# design.net
KiCad netlist of a schematic drawn in Altium Designer
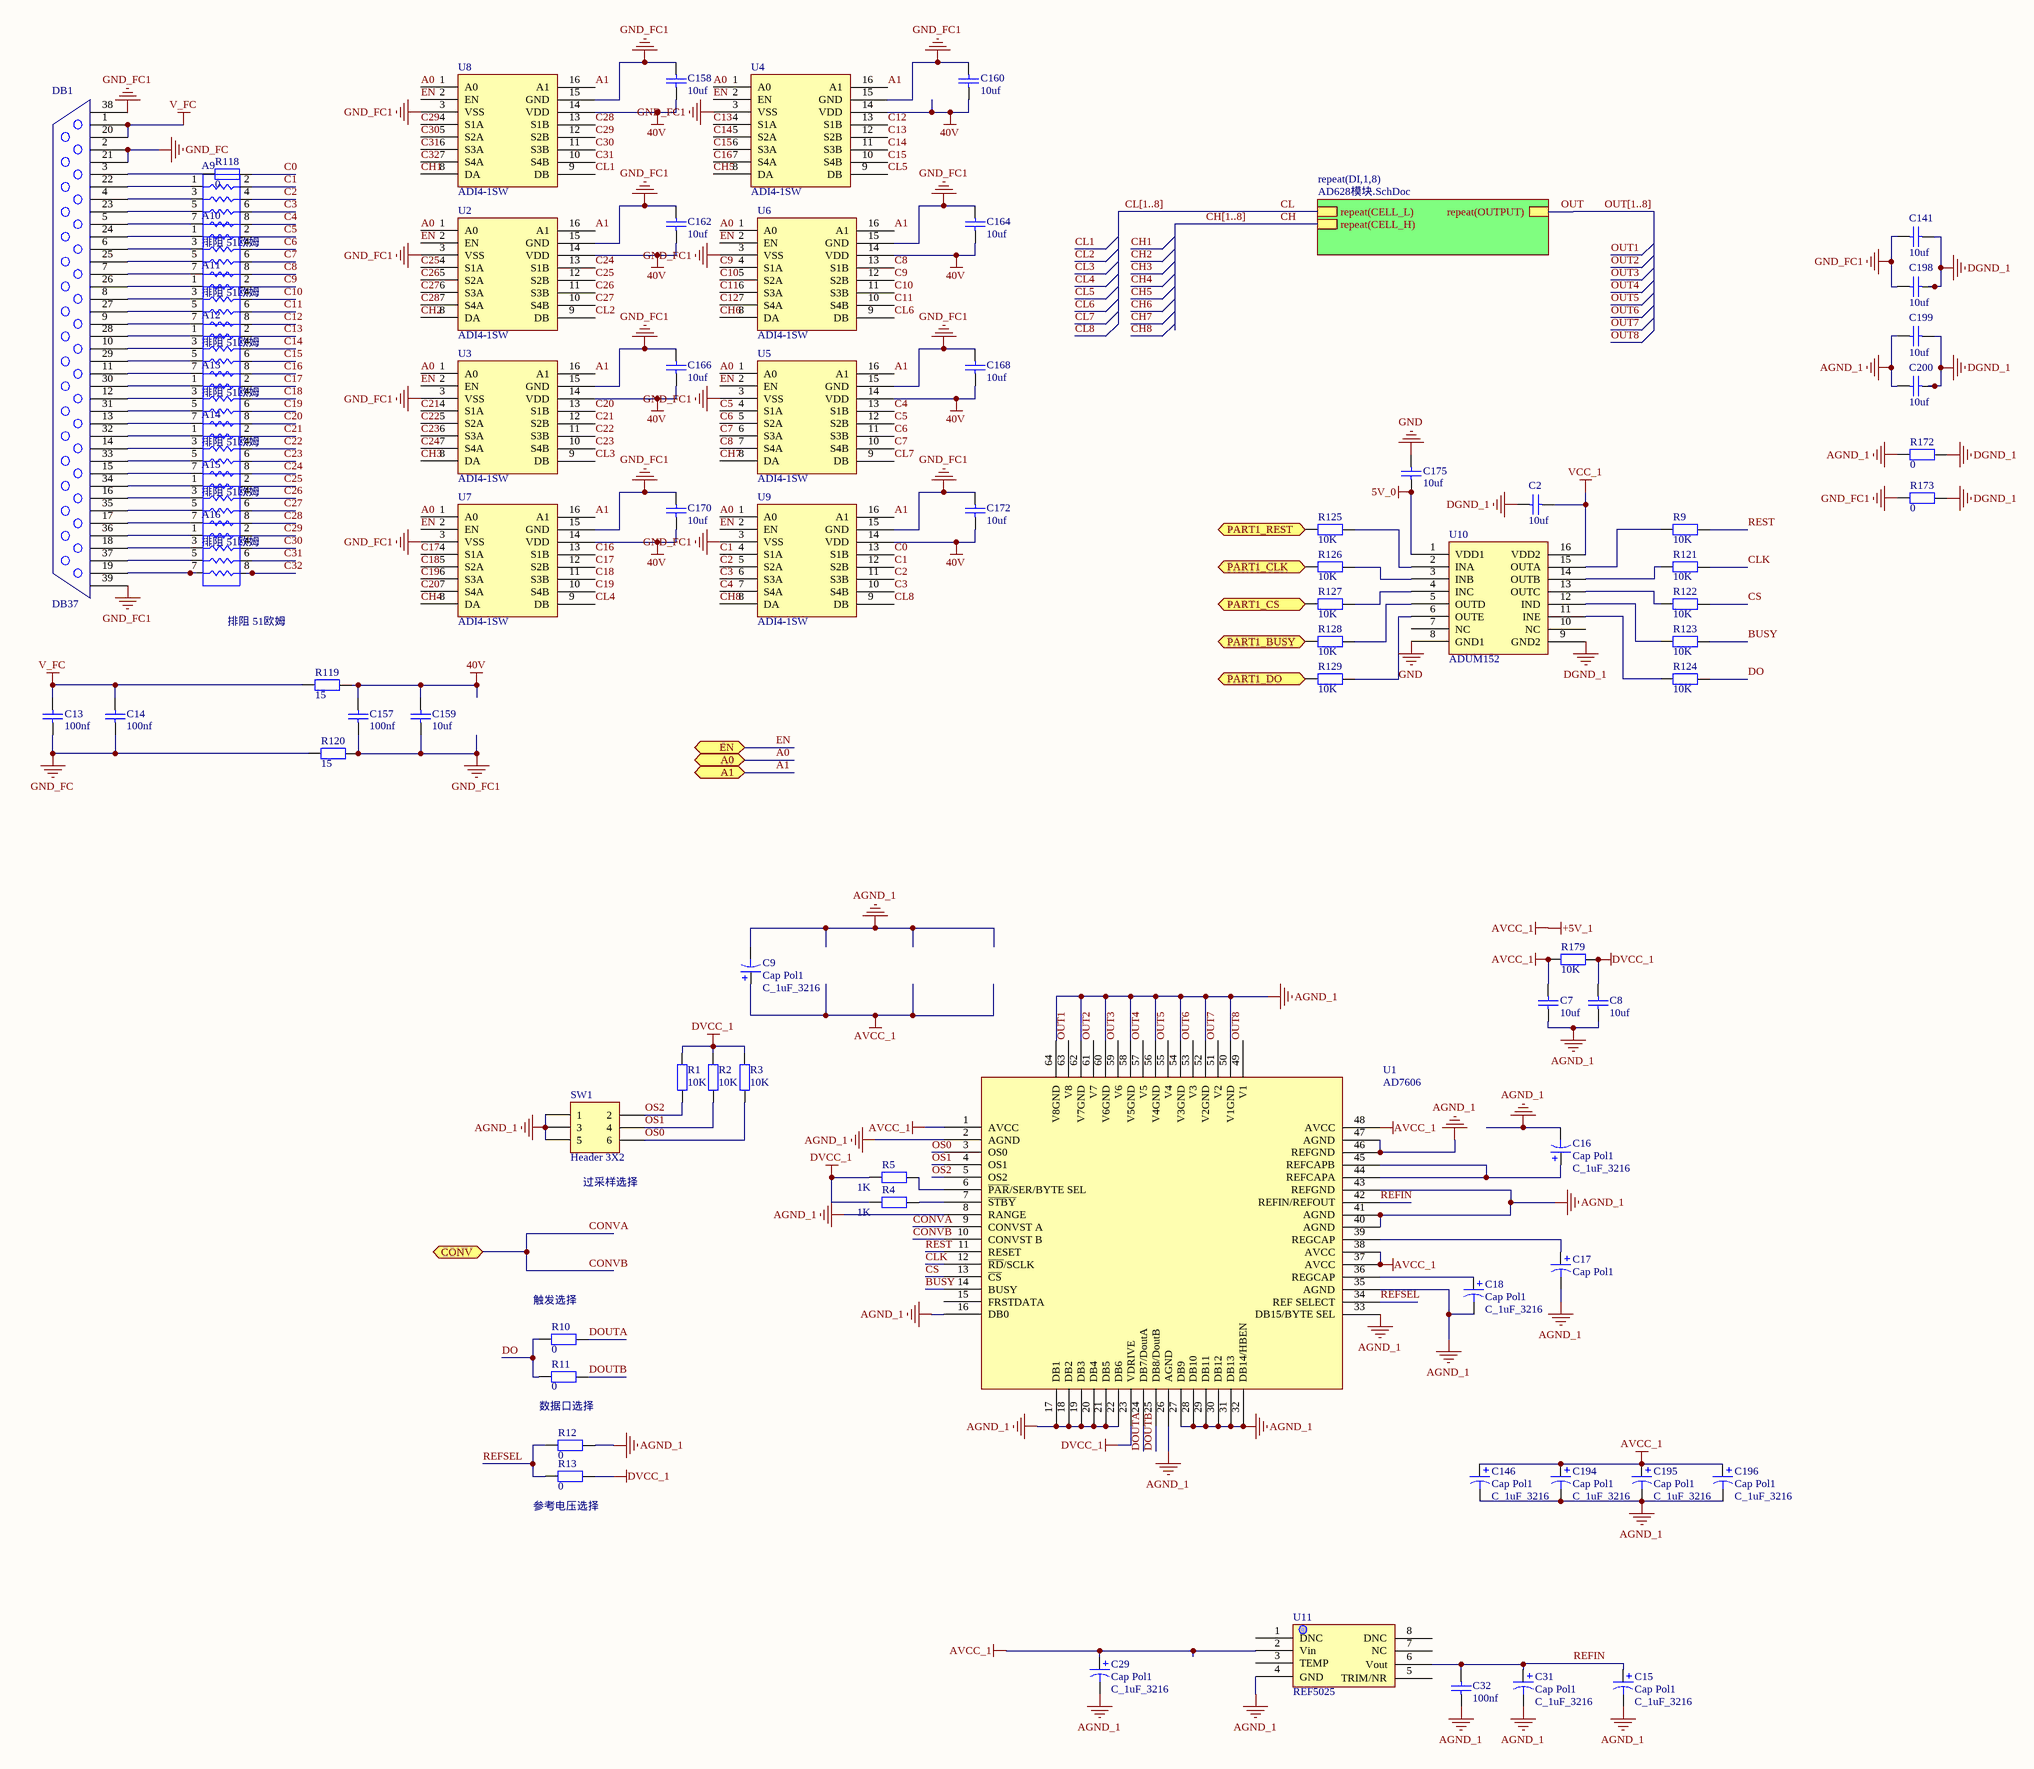
[diagram p0: 电池电压检测.SchDoc]

(export (version "E")
  (design (tool "Eeschema 10.0.6"))
  (components
    (comp (ref "A9")
      (value "排阻 51欧姆")
      (footprint "RCA03-4D")
      (libsource (lib "AD7606V23A") (part "RESPACK5"))
    )
    (comp (ref "A10")
      (value "排阻 51欧姆")
      (footprint "RCA03-4D")
      (libsource (lib "AD7606V23A") (part "RESPACK5"))
    )
    (comp (ref "A11")
      (value "排阻 51欧姆")
      (footprint "RCA03-4D")
      (libsource (lib "AD7606V23A") (part "RESPACK5"))
    )
    (comp (ref "A12")
      (value "排阻 51欧姆")
      (footprint "RCA03-4D")
      (libsource (lib "AD7606V23A") (part "RESPACK5"))
    )
    (comp (ref "A13")
      (value "排阻 51欧姆")
      (footprint "RCA03-4D")
      (libsource (lib "AD7606V23A") (part "RESPACK5"))
    )
    (comp (ref "A14")
      (value "排阻 51欧姆")
      (footprint "RCA03-4D")
      (libsource (lib "AD7606V23A") (part "RESPACK5"))
    )
    (comp (ref "A15")
      (value "排阻 51欧姆")
      (footprint "RCA03-4D")
      (libsource (lib "AD7606V23A") (part "RESPACK5"))
    )
    (comp (ref "A16")
      (value "排阻 51欧姆")
      (footprint "RCA03-4D")
      (libsource (lib "AD7606V23A") (part "RESPACK5"))
    )
    (comp (ref "C2")
      (value "10uf")
      (footprint "0805C")
      (description "Capacitor")
      (fields (field (name "Comment") "Cap") (field (name "PUBLISHER") "Altium Limited"))
      (libsource (lib "Miscellaneous Devices") (part "Cap"))
    )
    (comp (ref "C7")
      (value "10uf")
      (footprint "0805C")
      (description "Capacitor")
      (fields (field (name "Comment") "Cap") (field (name "PUBLISHER") "Altium Limited"))
      (libsource (lib "Miscellaneous Devices") (part "Cap"))
    )
    (comp (ref "C8")
      (value "10uf")
      (footprint "0805C")
      (description "Capacitor")
      (fields (field (name "Comment") "Cap") (field (name "PUBLISHER") "Altium Limited"))
      (libsource (lib "Miscellaneous Devices") (part "Cap"))
    )
    (comp (ref "C9")
      (value "Cap Pol1")
      (footprint "3216")
      (description "Polarized Capacitor (Radial)")
      (fields (field (name "ALTIUM_VALUE") "C_1uF_3216") (field (name "PUBLISHER") "Altium Limited"))
      (libsource (lib "AD7606V23A") (part "Cap Pol1"))
    )
    (comp (ref "C13")
      (value "100nf")
      (footprint "1812-C")
      (description "Capacitor")
      (fields (field (name "Comment") "Cap") (field (name "PUBLISHER") "Altium Limited"))
      (libsource (lib "Miscellaneous Devices") (part "Cap"))
    )
    (comp (ref "C14")
      (value "100nf")
      (footprint "1812-C")
      (description "Capacitor")
      (fields (field (name "Comment") "Cap") (field (name "PUBLISHER") "Altium Limited"))
      (libsource (lib "Miscellaneous Devices") (part "Cap"))
    )
    (comp (ref "C15")
      (value "Cap Pol1")
      (footprint "3216")
      (description "Polarized Capacitor (Radial)")
      (fields (field (name "ALTIUM_VALUE") "C_1uF_3216") (field (name "PUBLISHER") "Altium Limited"))
      (libsource (lib "AD7606V23A") (part "Cap Pol1"))
    )
    (comp (ref "C16")
      (value "Cap Pol1")
      (footprint "3216")
      (description "Polarized Capacitor (Radial)")
      (fields (field (name "ALTIUM_VALUE") "C_1uF_3216") (field (name "PUBLISHER") "Altium Limited"))
      (libsource (lib "AD7606V23A") (part "Cap Pol1"))
    )
    (comp (ref "C17")
      (value "Cap Pol1")
      (footprint "3216")
      (description "Polarized Capacitor (Radial)")
      (fields (field (name "PUBLISHER") "Altium Limited"))
      (libsource (lib "AD7606V23A") (part "Cap Pol1"))
    )
    (comp (ref "C18")
      (value "Cap Pol1")
      (footprint "3216")
      (description "Polarized Capacitor (Radial)")
      (fields (field (name "ALTIUM_VALUE") "C_1uF_3216") (field (name "PUBLISHER") "Altium Limited"))
      (libsource (lib "AD7606V23A") (part "Cap Pol1"))
    )
    (comp (ref "C29")
      (value "Cap Pol1")
      (footprint "3216")
      (description "Polarized Capacitor (Radial)")
      (fields (field (name "ALTIUM_VALUE") "C_1uF_3216") (field (name "PUBLISHER") "Altium Limited"))
      (libsource (lib "AD7606V23A") (part "Cap Pol1"))
    )
    (comp (ref "C31")
      (value "Cap Pol1")
      (footprint "3216")
      (description "Polarized Capacitor (Radial)")
      (fields (field (name "ALTIUM_VALUE") "C_1uF_3216") (field (name "PUBLISHER") "Altium Limited"))
      (libsource (lib "AD7606V23A") (part "Cap Pol1"))
    )
    (comp (ref "C32")
      (value "100nf")
      (footprint "0805C")
      (description "Capacitor")
      (fields (field (name "Comment") "Cap") (field (name "PUBLISHER") "Altium Limited"))
      (libsource (lib "Miscellaneous Devices") (part "Cap"))
    )
    (comp (ref "C141")
      (value "10uf")
      (footprint "0805C")
      (description "Capacitor")
      (fields (field (name "Comment") "Cap") (field (name "PUBLISHER") "Altium Limited"))
      (libsource (lib "Miscellaneous Devices") (part "Cap"))
    )
    (comp (ref "C146")
      (value "Cap Pol1")
      (footprint "3216")
      (description "Polarized Capacitor (Radial)")
      (fields (field (name "ALTIUM_VALUE") "C_1uF_3216") (field (name "PUBLISHER") "Altium Limited"))
      (libsource (lib "AD7606V23A") (part "Cap Pol1"))
    )
    (comp (ref "C157")
      (value "100nf")
      (footprint "1812-C")
      (description "Capacitor")
      (fields (field (name "Comment") "Cap") (field (name "PUBLISHER") "Altium Limited"))
      (libsource (lib "Miscellaneous Devices") (part "Cap"))
    )
    (comp (ref "C158")
      (value "10uf")
      (footprint "0805C")
      (description "Capacitor")
      (fields (field (name "Comment") "Cap") (field (name "PUBLISHER") "Altium Limited"))
      (libsource (lib "Miscellaneous Devices") (part "Cap"))
    )
    (comp (ref "C159")
      (value "10uf")
      (footprint "0805C")
      (description "Capacitor")
      (fields (field (name "Comment") "Cap") (field (name "PUBLISHER") "Altium Limited"))
      (libsource (lib "Miscellaneous Devices") (part "Cap"))
    )
    (comp (ref "C160")
      (value "10uf")
      (footprint "0805C")
      (description "Capacitor")
      (fields (field (name "Comment") "Cap") (field (name "PUBLISHER") "Altium Limited"))
      (libsource (lib "Miscellaneous Devices") (part "Cap"))
    )
    (comp (ref "C162")
      (value "10uf")
      (footprint "0805C")
      (description "Capacitor")
      (fields (field (name "Comment") "Cap") (field (name "PUBLISHER") "Altium Limited"))
      (libsource (lib "Miscellaneous Devices") (part "Cap"))
    )
    (comp (ref "C164")
      (value "10uf")
      (footprint "0805C")
      (description "Capacitor")
      (fields (field (name "Comment") "Cap") (field (name "PUBLISHER") "Altium Limited"))
      (libsource (lib "Miscellaneous Devices") (part "Cap"))
    )
    (comp (ref "C166")
      (value "10uf")
      (footprint "0805C")
      (description "Capacitor")
      (fields (field (name "Comment") "Cap") (field (name "PUBLISHER") "Altium Limited"))
      (libsource (lib "Miscellaneous Devices") (part "Cap"))
    )
    (comp (ref "C168")
      (value "10uf")
      (footprint "0805C")
      (description "Capacitor")
      (fields (field (name "Comment") "Cap") (field (name "PUBLISHER") "Altium Limited"))
      (libsource (lib "Miscellaneous Devices") (part "Cap"))
    )
    (comp (ref "C170")
      (value "10uf")
      (footprint "0805C")
      (description "Capacitor")
      (fields (field (name "Comment") "Cap") (field (name "PUBLISHER") "Altium Limited"))
      (libsource (lib "Miscellaneous Devices") (part "Cap"))
    )
    (comp (ref "C172")
      (value "10uf")
      (footprint "0805C")
      (description "Capacitor")
      (fields (field (name "Comment") "Cap") (field (name "PUBLISHER") "Altium Limited"))
      (libsource (lib "Miscellaneous Devices") (part "Cap"))
    )
    (comp (ref "C175")
      (value "10uf")
      (footprint "0805C")
      (description "Capacitor")
      (fields (field (name "Comment") "Cap") (field (name "PUBLISHER") "Altium Limited"))
      (libsource (lib "Miscellaneous Devices") (part "Cap"))
    )
    (comp (ref "C194")
      (value "Cap Pol1")
      (footprint "3216")
      (description "Polarized Capacitor (Radial)")
      (fields (field (name "ALTIUM_VALUE") "C_1uF_3216") (field (name "PUBLISHER") "Altium Limited"))
      (libsource (lib "AD7606V23A") (part "Cap Pol1"))
    )
    (comp (ref "C195")
      (value "Cap Pol1")
      (footprint "3216")
      (description "Polarized Capacitor (Radial)")
      (fields (field (name "ALTIUM_VALUE") "C_1uF_3216") (field (name "PUBLISHER") "Altium Limited"))
      (libsource (lib "AD7606V23A") (part "Cap Pol1"))
    )
    (comp (ref "C196")
      (value "Cap Pol1")
      (footprint "3216")
      (description "Polarized Capacitor (Radial)")
      (fields (field (name "ALTIUM_VALUE") "C_1uF_3216") (field (name "PUBLISHER") "Altium Limited"))
      (libsource (lib "AD7606V23A") (part "Cap Pol1"))
    )
    (comp (ref "C198")
      (value "10uf")
      (footprint "0805C")
      (description "Capacitor")
      (fields (field (name "Comment") "Cap") (field (name "PUBLISHER") "Altium Limited"))
      (libsource (lib "Miscellaneous Devices") (part "Cap"))
    )
    (comp (ref "C199")
      (value "10uf")
      (footprint "0805C")
      (description "Capacitor")
      (fields (field (name "Comment") "Cap") (field (name "PUBLISHER") "Altium Limited"))
      (libsource (lib "Miscellaneous Devices") (part "Cap"))
    )
    (comp (ref "C200")
      (value "10uf")
      (footprint "0805C")
      (description "Capacitor")
      (fields (field (name "Comment") "Cap") (field (name "PUBLISHER") "Altium Limited"))
      (libsource (lib "Miscellaneous Devices") (part "Cap"))
    )
    (comp (ref "DB1") (value "DB37") (footprint "DB37") (libsource (lib "connect") (part "DB37")))
    (comp (ref "R1")
      (value "10K")
      (footprint "0805R")
      (description "Resistor")
      (fields (field (name "Comment") "Res2") (field (name "PUBLISHER") "Altium Limited"))
      (libsource (lib "Miscellaneous Devices") (part "Res2"))
    )
    (comp (ref "R2")
      (value "10K")
      (footprint "0805R")
      (description "Resistor")
      (fields (field (name "Comment") "Res2") (field (name "PUBLISHER") "Altium Limited"))
      (libsource (lib "Miscellaneous Devices") (part "Res2"))
    )
    (comp (ref "R3")
      (value "10K")
      (footprint "0805R")
      (description "Resistor")
      (fields (field (name "Comment") "Res2") (field (name "PUBLISHER") "Altium Limited"))
      (libsource (lib "Miscellaneous Devices") (part "Res2"))
    )
    (comp (ref "R4")
      (value "1K")
      (footprint "0805R")
      (description "Resistor")
      (fields (field (name "Comment") "Res2") (field (name "PUBLISHER") "Altium Limited"))
      (libsource (lib "") (part "Res2_2"))
    )
    (comp (ref "R5")
      (value "1K")
      (footprint "0805R")
      (description "Resistor")
      (fields (field (name "Comment") "Res2") (field (name "PUBLISHER") "Altium Limited"))
      (libsource (lib "") (part "Res2_2"))
    )
    (comp (ref "R9")
      (value "10K")
      (footprint "0805R")
      (description "Resistor")
      (fields (field (name "Comment") "Res2") (field (name "PUBLISHER") "Altium Limited"))
      (libsource (lib "Miscellaneous Devices") (part "Res2"))
    )
    (comp (ref "R10")
      (value "0")
      (footprint "0805R")
      (description "Resistor")
      (fields (field (name "Comment") "Res2") (field (name "PUBLISHER") "Altium Limited"))
      (libsource (lib "") (part "Res2_1"))
    )
    (comp (ref "R11")
      (value "0")
      (footprint "0805R")
      (description "Resistor")
      (fields (field (name "Comment") "Res2") (field (name "PUBLISHER") "Altium Limited"))
      (libsource (lib "") (part "Res2_1"))
    )
    (comp (ref "R12")
      (value "0")
      (footprint "0805R")
      (description "Resistor")
      (fields (field (name "Comment") "Res2") (field (name "PUBLISHER") "Altium Limited"))
      (libsource (lib "") (part "Res2_2"))
    )
    (comp (ref "R13")
      (value "0")
      (footprint "0805R")
      (description "Resistor")
      (fields (field (name "Comment") "Res2") (field (name "PUBLISHER") "Altium Limited"))
      (libsource (lib "") (part "Res2_2"))
    )
    (comp (ref "R118")
      (value "0")
      (footprint "0603AR")
      (description "Resistor")
      (fields (field (name "Comment") "Res2") (field (name "PUBLISHER") "Altium Limited"))
      (libsource (lib "") (part "Res2_2"))
    )
    (comp (ref "R119")
      (value "15")
      (footprint "0805R")
      (description "Resistor")
      (fields (field (name "Comment") "Res2") (field (name "PUBLISHER") "Altium Limited"))
      (libsource (lib "") (part "Res2_1"))
    )
    (comp (ref "R120")
      (value "15")
      (footprint "0805R")
      (description "Resistor")
      (fields (field (name "Comment") "Res2") (field (name "PUBLISHER") "Altium Limited"))
      (libsource (lib "") (part "Res2_1"))
    )
    (comp (ref "R121")
      (value "10K")
      (footprint "0805R")
      (description "Resistor")
      (fields (field (name "Comment") "Res2") (field (name "PUBLISHER") "Altium Limited"))
      (libsource (lib "Miscellaneous Devices") (part "Res2"))
    )
    (comp (ref "R122")
      (value "10K")
      (footprint "0805R")
      (description "Resistor")
      (fields (field (name "Comment") "Res2") (field (name "PUBLISHER") "Altium Limited"))
      (libsource (lib "Miscellaneous Devices") (part "Res2"))
    )
    (comp (ref "R123")
      (value "10K")
      (footprint "0805R")
      (description "Resistor")
      (fields (field (name "Comment") "Res2") (field (name "PUBLISHER") "Altium Limited"))
      (libsource (lib "Miscellaneous Devices") (part "Res2"))
    )
    (comp (ref "R124")
      (value "10K")
      (footprint "0805R")
      (description "Resistor")
      (fields (field (name "Comment") "Res2") (field (name "PUBLISHER") "Altium Limited"))
      (libsource (lib "Miscellaneous Devices") (part "Res2"))
    )
    (comp (ref "R125")
      (value "10K")
      (footprint "0805R")
      (description "Resistor")
      (fields (field (name "Comment") "Res2") (field (name "PUBLISHER") "Altium Limited"))
      (libsource (lib "Miscellaneous Devices") (part "Res2"))
    )
    (comp (ref "R126")
      (value "10K")
      (footprint "0805R")
      (description "Resistor")
      (fields (field (name "Comment") "Res2") (field (name "PUBLISHER") "Altium Limited"))
      (libsource (lib "Miscellaneous Devices") (part "Res2"))
    )
    (comp (ref "R127")
      (value "10K")
      (footprint "0805R")
      (description "Resistor")
      (fields (field (name "Comment") "Res2") (field (name "PUBLISHER") "Altium Limited"))
      (libsource (lib "Miscellaneous Devices") (part "Res2"))
    )
    (comp (ref "R128")
      (value "10K")
      (footprint "0805R")
      (description "Resistor")
      (fields (field (name "Comment") "Res2") (field (name "PUBLISHER") "Altium Limited"))
      (libsource (lib "Miscellaneous Devices") (part "Res2"))
    )
    (comp (ref "R129")
      (value "10K")
      (footprint "0805R")
      (description "Resistor")
      (fields (field (name "Comment") "Res2") (field (name "PUBLISHER") "Altium Limited"))
      (libsource (lib "Miscellaneous Devices") (part "Res2"))
    )
    (comp (ref "R172")
      (value "0")
      (footprint "0805R")
      (description "Resistor")
      (fields (field (name "Comment") "Res2") (field (name "PUBLISHER") "Altium Limited"))
      (libsource (lib "Miscellaneous Devices") (part "Res2"))
    )
    (comp (ref "R173")
      (value "0")
      (footprint "0805R")
      (description "Resistor")
      (fields (field (name "Comment") "Res2") (field (name "PUBLISHER") "Altium Limited"))
      (libsource (lib "Miscellaneous Devices") (part "Res2"))
    )
    (comp (ref "R179")
      (value "10K")
      (footprint "0805R")
      (description "Resistor")
      (fields (field (name "Comment") "Res2") (field (name "PUBLISHER") "Altium Limited"))
      (libsource (lib "Miscellaneous Devices") (part "Res2"))
    )
    (comp (ref "SW1")
      (value "Header 3X2")
      (footprint "SW_6")
      (description "Header, 3-Pin, Dual row")
      (fields (field (name "PUBLISHER") "Altium Limited"))
      (libsource (lib "Miscellaneous Connectors") (part "Header 3X2"))
    )
    (comp (ref "U1") (value "AD7606") (footprint "TQFP64") (libsource (lib "AD7606V23A") (part "AD7606")))
    (comp (ref "U2") (value "ADI4-1SW") (footprint "TSSOP16") (libsource (lib "ic_lib") (part "ADI4-1SW")))
    (comp (ref "U3") (value "ADI4-1SW") (footprint "TSSOP16") (libsource (lib "ic_lib") (part "ADI4-1SW")))
    (comp (ref "U4") (value "ADI4-1SW") (footprint "TSSOP16") (libsource (lib "ic_lib") (part "ADI4-1SW")))
    (comp (ref "U5") (value "ADI4-1SW") (footprint "TSSOP16") (libsource (lib "ic_lib") (part "ADI4-1SW")))
    (comp (ref "U6") (value "ADI4-1SW") (footprint "TSSOP16") (libsource (lib "ic_lib") (part "ADI4-1SW")))
    (comp (ref "U7") (value "ADI4-1SW") (footprint "TSSOP16") (libsource (lib "ic_lib") (part "ADI4-1SW")))
    (comp (ref "U8") (value "ADI4-1SW") (footprint "TSSOP16") (libsource (lib "ic_lib") (part "ADI4-1SW")))
    (comp (ref "U9") (value "ADI4-1SW") (footprint "TSSOP16") (libsource (lib "ic_lib") (part "ADI4-1SW")))
    (comp (ref "U10") (value "ADUM152") (footprint "SO16NB") (libsource (lib "ic_lib") (part "ADUM152")))
    (comp (ref "U11") (value "REF5025") (footprint "SOP8") (libsource (lib "AD7606V23A") (part "REF5025")))
  )
  (nets
    (net (code "1") (name "+5V_1") (class "Default")
      (node (ref "C146") (pin "1") (pinfunction "1_1") (pintype "passive"))
      (node (ref "C194") (pin "1") (pinfunction "1_1") (pintype "passive"))
      (node (ref "C195") (pin "1") (pinfunction "1_1") (pintype "passive"))
      (node (ref "C196") (pin "1") (pinfunction "1_1") (pintype "passive"))
      (node (ref "C29") (pin "1") (pinfunction "1_1") (pintype "passive"))
      (node (ref "C7") (pin "2") (pinfunction "2_2") (pintype "passive"))
      (node (ref "C9") (pin "1") (pinfunction "1_1") (pintype "passive"))
      (node (ref "R179") (pin "2") (pinfunction "2_2") (pintype "passive"))
      (node (ref "U1") (pin "1") (pinfunction "AVCC_1") (pintype "passive"))
      (node (ref "U1") (pin "37") (pinfunction "AVCC_37") (pintype "passive"))
      (node (ref "U1") (pin "38") (pinfunction "AVCC_38") (pintype "passive"))
      (node (ref "U1") (pin "48") (pinfunction "AVCC_48") (pintype "passive"))
      (node (ref "U11") (pin "2") (pinfunction "Vin_2") (pintype "passive"))
    )
    (net (code "2") (name "/A0") (class "Default")
      (node (ref "U2") (pin "1") (pinfunction "A0_1") (pintype "passive"))
      (node (ref "U3") (pin "1") (pinfunction "A0_1") (pintype "passive"))
      (node (ref "U4") (pin "1") (pinfunction "A0_1") (pintype "passive"))
      (node (ref "U5") (pin "1") (pinfunction "A0_1") (pintype "passive"))
      (node (ref "U6") (pin "1") (pinfunction "A0_1") (pintype "passive"))
      (node (ref "U7") (pin "1") (pinfunction "A0_1") (pintype "passive"))
      (node (ref "U8") (pin "1") (pinfunction "A0_1") (pintype "passive"))
      (node (ref "U9") (pin "1") (pinfunction "A0_1") (pintype "passive"))
    )
    (net (code "3") (name "/A1") (class "Default")
      (node (ref "U2") (pin "16") (pinfunction "A1_16") (pintype "passive"))
      (node (ref "U3") (pin "16") (pinfunction "A1_16") (pintype "passive"))
      (node (ref "U4") (pin "16") (pinfunction "A1_16") (pintype "passive"))
      (node (ref "U5") (pin "16") (pinfunction "A1_16") (pintype "passive"))
      (node (ref "U6") (pin "16") (pinfunction "A1_16") (pintype "passive"))
      (node (ref "U7") (pin "16") (pinfunction "A1_16") (pintype "passive"))
      (node (ref "U8") (pin "16") (pinfunction "A1_16") (pintype "passive"))
      (node (ref "U9") (pin "16") (pinfunction "A1_16") (pintype "passive"))
    )
    (net (code "4") (name "/BUSY") (class "Default")
      (node (ref "R123") (pin "1") (pinfunction "1_1") (pintype "passive"))
      (node (ref "U1") (pin "14") (pinfunction "BUSY_14") (pintype "passive"))
    )
    (net (code "5") (name "/C0") (class "Default")
      (node (ref "R118") (pin "1") (pinfunction "1_1") (pintype "passive"))
      (node (ref "U9") (pin "13") (pinfunction "S1B_13") (pintype "passive"))
    )
    (net (code "6") (name "/C1") (class "Default")
      (node (ref "A9") (pin "2") (pinfunction "2_2") (pintype "passive"))
      (node (ref "U9") (pin "12") (pinfunction "S2B_12") (pintype "passive"))
      (node (ref "U9") (pin "4") (pinfunction "S1A_4") (pintype "passive"))
    )
    (net (code "7") (name "/C2") (class "Default")
      (node (ref "A9") (pin "4") (pinfunction "4_4") (pintype "passive"))
      (node (ref "U9") (pin "11") (pinfunction "S3B_11") (pintype "passive"))
      (node (ref "U9") (pin "5") (pinfunction "S2A_5") (pintype "passive"))
    )
    (net (code "8") (name "/C3") (class "Default")
      (node (ref "A9") (pin "6") (pinfunction "8_6") (pintype "passive"))
      (node (ref "U9") (pin "10") (pinfunction "S4B_10") (pintype "passive"))
      (node (ref "U9") (pin "6") (pinfunction "S3A_6") (pintype "passive"))
    )
    (net (code "9") (name "/C4") (class "Default")
      (node (ref "A9") (pin "8") (pinfunction "8_8") (pintype "passive"))
      (node (ref "U5") (pin "13") (pinfunction "S1B_13") (pintype "passive"))
      (node (ref "U9") (pin "7") (pinfunction "S4A_7") (pintype "passive"))
    )
    (net (code "10") (name "/C5") (class "Default")
      (node (ref "A10") (pin "2") (pinfunction "2_2") (pintype "passive"))
      (node (ref "U5") (pin "12") (pinfunction "S2B_12") (pintype "passive"))
      (node (ref "U5") (pin "4") (pinfunction "S1A_4") (pintype "passive"))
    )
    (net (code "11") (name "/C6") (class "Default")
      (node (ref "A10") (pin "4") (pinfunction "4_4") (pintype "passive"))
      (node (ref "U5") (pin "11") (pinfunction "S3B_11") (pintype "passive"))
      (node (ref "U5") (pin "5") (pinfunction "S2A_5") (pintype "passive"))
    )
    (net (code "12") (name "/C7") (class "Default")
      (node (ref "A10") (pin "6") (pinfunction "8_6") (pintype "passive"))
      (node (ref "U5") (pin "10") (pinfunction "S4B_10") (pintype "passive"))
      (node (ref "U5") (pin "6") (pinfunction "S3A_6") (pintype "passive"))
    )
    (net (code "13") (name "/C8") (class "Default")
      (node (ref "A10") (pin "8") (pinfunction "8_8") (pintype "passive"))
      (node (ref "U5") (pin "7") (pinfunction "S4A_7") (pintype "passive"))
      (node (ref "U6") (pin "13") (pinfunction "S1B_13") (pintype "passive"))
    )
    (net (code "14") (name "/C9") (class "Default")
      (node (ref "A11") (pin "2") (pinfunction "2_2") (pintype "passive"))
      (node (ref "U6") (pin "12") (pinfunction "S2B_12") (pintype "passive"))
      (node (ref "U6") (pin "4") (pinfunction "S1A_4") (pintype "passive"))
    )
    (net (code "15") (name "/C10") (class "Default")
      (node (ref "A11") (pin "4") (pinfunction "4_4") (pintype "passive"))
      (node (ref "U6") (pin "11") (pinfunction "S3B_11") (pintype "passive"))
      (node (ref "U6") (pin "5") (pinfunction "S2A_5") (pintype "passive"))
    )
    (net (code "16") (name "/C11") (class "Default")
      (node (ref "A11") (pin "6") (pinfunction "8_6") (pintype "passive"))
      (node (ref "U6") (pin "10") (pinfunction "S4B_10") (pintype "passive"))
      (node (ref "U6") (pin "6") (pinfunction "S3A_6") (pintype "passive"))
    )
    (net (code "17") (name "/C12") (class "Default")
      (node (ref "A11") (pin "8") (pinfunction "8_8") (pintype "passive"))
      (node (ref "U4") (pin "13") (pinfunction "S1B_13") (pintype "passive"))
      (node (ref "U6") (pin "7") (pinfunction "S4A_7") (pintype "passive"))
    )
    (net (code "18") (name "/C13") (class "Default")
      (node (ref "A12") (pin "2") (pinfunction "2_2") (pintype "passive"))
      (node (ref "U4") (pin "12") (pinfunction "S2B_12") (pintype "passive"))
      (node (ref "U4") (pin "4") (pinfunction "S1A_4") (pintype "passive"))
    )
    (net (code "19") (name "/C14") (class "Default")
      (node (ref "A12") (pin "4") (pinfunction "4_4") (pintype "passive"))
      (node (ref "U4") (pin "11") (pinfunction "S3B_11") (pintype "passive"))
      (node (ref "U4") (pin "5") (pinfunction "S2A_5") (pintype "passive"))
    )
    (net (code "20") (name "/C15") (class "Default")
      (node (ref "A12") (pin "6") (pinfunction "8_6") (pintype "passive"))
      (node (ref "U4") (pin "10") (pinfunction "S4B_10") (pintype "passive"))
      (node (ref "U4") (pin "6") (pinfunction "S3A_6") (pintype "passive"))
    )
    (net (code "21") (name "/C16") (class "Default")
      (node (ref "A12") (pin "8") (pinfunction "8_8") (pintype "passive"))
      (node (ref "U4") (pin "7") (pinfunction "S4A_7") (pintype "passive"))
      (node (ref "U7") (pin "13") (pinfunction "S1B_13") (pintype "passive"))
    )
    (net (code "22") (name "/C17") (class "Default")
      (node (ref "A13") (pin "2") (pinfunction "2_2") (pintype "passive"))
      (node (ref "U7") (pin "12") (pinfunction "S2B_12") (pintype "passive"))
      (node (ref "U7") (pin "4") (pinfunction "S1A_4") (pintype "passive"))
    )
    (net (code "23") (name "/C18") (class "Default")
      (node (ref "A13") (pin "4") (pinfunction "4_4") (pintype "passive"))
      (node (ref "U7") (pin "11") (pinfunction "S3B_11") (pintype "passive"))
      (node (ref "U7") (pin "5") (pinfunction "S2A_5") (pintype "passive"))
    )
    (net (code "24") (name "/C19") (class "Default")
      (node (ref "A13") (pin "6") (pinfunction "8_6") (pintype "passive"))
      (node (ref "U7") (pin "10") (pinfunction "S4B_10") (pintype "passive"))
      (node (ref "U7") (pin "6") (pinfunction "S3A_6") (pintype "passive"))
    )
    (net (code "25") (name "/C20") (class "Default")
      (node (ref "A13") (pin "8") (pinfunction "8_8") (pintype "passive"))
      (node (ref "U3") (pin "13") (pinfunction "S1B_13") (pintype "passive"))
      (node (ref "U7") (pin "7") (pinfunction "S4A_7") (pintype "passive"))
    )
    (net (code "26") (name "/C21") (class "Default")
      (node (ref "A14") (pin "2") (pinfunction "2_2") (pintype "passive"))
      (node (ref "U3") (pin "12") (pinfunction "S2B_12") (pintype "passive"))
      (node (ref "U3") (pin "4") (pinfunction "S1A_4") (pintype "passive"))
    )
    (net (code "27") (name "/C22") (class "Default")
      (node (ref "A14") (pin "4") (pinfunction "4_4") (pintype "passive"))
      (node (ref "U3") (pin "11") (pinfunction "S3B_11") (pintype "passive"))
      (node (ref "U3") (pin "5") (pinfunction "S2A_5") (pintype "passive"))
    )
    (net (code "28") (name "/C23") (class "Default")
      (node (ref "A14") (pin "6") (pinfunction "8_6") (pintype "passive"))
      (node (ref "U3") (pin "10") (pinfunction "S4B_10") (pintype "passive"))
      (node (ref "U3") (pin "6") (pinfunction "S3A_6") (pintype "passive"))
    )
    (net (code "29") (name "/C24") (class "Default")
      (node (ref "A14") (pin "8") (pinfunction "8_8") (pintype "passive"))
      (node (ref "U2") (pin "13") (pinfunction "S1B_13") (pintype "passive"))
      (node (ref "U3") (pin "7") (pinfunction "S4A_7") (pintype "passive"))
    )
    (net (code "30") (name "/C25") (class "Default")
      (node (ref "A15") (pin "2") (pinfunction "2_2") (pintype "passive"))
      (node (ref "U2") (pin "12") (pinfunction "S2B_12") (pintype "passive"))
      (node (ref "U2") (pin "4") (pinfunction "S1A_4") (pintype "passive"))
    )
    (net (code "31") (name "/C26") (class "Default")
      (node (ref "A15") (pin "4") (pinfunction "4_4") (pintype "passive"))
      (node (ref "U2") (pin "11") (pinfunction "S3B_11") (pintype "passive"))
      (node (ref "U2") (pin "5") (pinfunction "S2A_5") (pintype "passive"))
    )
    (net (code "32") (name "/C27") (class "Default")
      (node (ref "A15") (pin "6") (pinfunction "8_6") (pintype "passive"))
      (node (ref "U2") (pin "10") (pinfunction "S4B_10") (pintype "passive"))
      (node (ref "U2") (pin "6") (pinfunction "S3A_6") (pintype "passive"))
    )
    (net (code "33") (name "/C28") (class "Default")
      (node (ref "A15") (pin "8") (pinfunction "8_8") (pintype "passive"))
      (node (ref "U2") (pin "7") (pinfunction "S4A_7") (pintype "passive"))
      (node (ref "U8") (pin "13") (pinfunction "S1B_13") (pintype "passive"))
    )
    (net (code "34") (name "/C29") (class "Default")
      (node (ref "A16") (pin "2") (pinfunction "2_2") (pintype "passive"))
      (node (ref "U8") (pin "12") (pinfunction "S2B_12") (pintype "passive"))
      (node (ref "U8") (pin "4") (pinfunction "S1A_4") (pintype "passive"))
    )
    (net (code "35") (name "/C30") (class "Default")
      (node (ref "A16") (pin "4") (pinfunction "4_4") (pintype "passive"))
      (node (ref "U8") (pin "11") (pinfunction "S3B_11") (pintype "passive"))
      (node (ref "U8") (pin "5") (pinfunction "S2A_5") (pintype "passive"))
    )
    (net (code "36") (name "/C31") (class "Default")
      (node (ref "A16") (pin "6") (pinfunction "8_6") (pintype "passive"))
      (node (ref "U8") (pin "10") (pinfunction "S4B_10") (pintype "passive"))
      (node (ref "U8") (pin "6") (pinfunction "S3A_6") (pintype "passive"))
    )
    (net (code "37") (name "/C32") (class "Default")
      (node (ref "A16") (pin "8") (pinfunction "8_8") (pintype "passive"))
      (node (ref "U8") (pin "7") (pinfunction "S4A_7") (pintype "passive"))
    )
    (net (code "39") (name "/CH1") (class "Default")
      (node (ref "U8") (pin "8") (pinfunction "DA_8") (pintype "passive"))
    )
    (net (code "40") (name "/CH2") (class "Default")
      (node (ref "U2") (pin "8") (pinfunction "DA_8") (pintype "passive"))
    )
    (net (code "41") (name "/CH3") (class "Default")
      (node (ref "U3") (pin "8") (pinfunction "DA_8") (pintype "passive"))
    )
    (net (code "42") (name "/CH4") (class "Default")
      (node (ref "U7") (pin "8") (pinfunction "DA_8") (pintype "passive"))
    )
    (net (code "43") (name "/CH5") (class "Default")
      (node (ref "U4") (pin "8") (pinfunction "DA_8") (pintype "passive"))
    )
    (net (code "44") (name "/CH6") (class "Default")
      (node (ref "U6") (pin "8") (pinfunction "DA_8") (pintype "passive"))
    )
    (net (code "45") (name "/CH7") (class "Default")
      (node (ref "U5") (pin "8") (pinfunction "DA_8") (pintype "passive"))
    )
    (net (code "46") (name "/CH8") (class "Default")
      (node (ref "U9") (pin "8") (pinfunction "DA_8") (pintype "passive"))
    )
    (net (code "49") (name "/CL1") (class "Default")
      (node (ref "U8") (pin "9") (pinfunction "DB_9") (pintype "passive"))
    )
    (net (code "50") (name "/CL2") (class "Default")
      (node (ref "U2") (pin "9") (pinfunction "DB_9") (pintype "passive"))
    )
    (net (code "51") (name "/CL3") (class "Default")
      (node (ref "U3") (pin "9") (pinfunction "DB_9") (pintype "passive"))
    )
    (net (code "52") (name "/CL4") (class "Default")
      (node (ref "U7") (pin "9") (pinfunction "DB_9") (pintype "passive"))
    )
    (net (code "53") (name "/CL5") (class "Default")
      (node (ref "U4") (pin "9") (pinfunction "DB_9") (pintype "passive"))
    )
    (net (code "54") (name "/CL6") (class "Default")
      (node (ref "U6") (pin "9") (pinfunction "DB_9") (pintype "passive"))
    )
    (net (code "55") (name "/CL7") (class "Default")
      (node (ref "U5") (pin "9") (pinfunction "DB_9") (pintype "passive"))
    )
    (net (code "56") (name "/CL8") (class "Default")
      (node (ref "U9") (pin "9") (pinfunction "DB_9") (pintype "passive"))
    )
    (net (code "57") (name "/CLK") (class "Default")
      (node (ref "R121") (pin "1") (pinfunction "1_1") (pintype "passive"))
      (node (ref "U1") (pin "12") (pinfunction "~{RD}/SCLK_12") (pintype "passive"))
    )
    (net (code "59") (name "/CONVA") (class "Default")
      (node (ref "U1") (pin "10") (pinfunction "CONVST_B_10") (pintype "passive"))
      (node (ref "U1") (pin "9") (pinfunction "CONVST_A_9") (pintype "passive"))
    )
    (net (code "60") (name "/CS") (class "Default")
      (node (ref "R122") (pin "1") (pinfunction "1_1") (pintype "passive"))
      (node (ref "U1") (pin "13") (pinfunction "~{CS}_13") (pintype "passive"))
    )
    (net (code "61") (name "/DO") (class "Default")
      (node (ref "R10") (pin "1") (pinfunction "1_1") (pintype "passive"))
      (node (ref "R11") (pin "1") (pinfunction "1_1") (pintype "passive"))
      (node (ref "R124") (pin "1") (pinfunction "1_1") (pintype "passive"))
    )
    (net (code "62") (name "/DOUTA") (class "Default")
      (node (ref "R10") (pin "2") (pinfunction "2_2") (pintype "passive"))
      (node (ref "U1") (pin "24") (pinfunction "DB7/DoutA_24") (pintype "passive"))
    )
    (net (code "63") (name "/DOUTB") (class "Default")
      (node (ref "R11") (pin "2") (pinfunction "2_2") (pintype "passive"))
      (node (ref "U1") (pin "25") (pinfunction "DB8/DoutB_25") (pintype "passive"))
    )
    (net (code "64") (name "/EN") (class "Default")
      (node (ref "U2") (pin "2") (pinfunction "EN_2") (pintype "passive"))
      (node (ref "U3") (pin "2") (pinfunction "EN_2") (pintype "passive"))
      (node (ref "U4") (pin "2") (pinfunction "EN_2") (pintype "passive"))
      (node (ref "U5") (pin "2") (pinfunction "EN_2") (pintype "passive"))
      (node (ref "U6") (pin "2") (pinfunction "EN_2") (pintype "passive"))
      (node (ref "U7") (pin "2") (pinfunction "EN_2") (pintype "passive"))
      (node (ref "U8") (pin "2") (pinfunction "EN_2") (pintype "passive"))
      (node (ref "U9") (pin "2") (pinfunction "EN_2") (pintype "passive"))
    )
    (net (code "65") (name "/OS0") (class "Default")
      (node (ref "R3") (pin "2") (pinfunction "2_2") (pintype "passive"))
      (node (ref "SW1") (pin "6") (pinfunction "6_6") (pintype "passive"))
      (node (ref "U1") (pin "3") (pinfunction "OS0_3") (pintype "passive"))
    )
    (net (code "66") (name "/OS1") (class "Default")
      (node (ref "R2") (pin "2") (pinfunction "2_2") (pintype "passive"))
      (node (ref "SW1") (pin "4") (pinfunction "4_4") (pintype "passive"))
      (node (ref "U1") (pin "4") (pinfunction "OS1_4") (pintype "passive"))
    )
    (net (code "67") (name "/OS2") (class "Default")
      (node (ref "R1") (pin "2") (pinfunction "2_2") (pintype "passive"))
      (node (ref "SW1") (pin "2") (pinfunction "2_2") (pintype "passive"))
      (node (ref "U1") (pin "5") (pinfunction "OS2_5") (pintype "passive"))
    )
    (net (code "69") (name "/OUT1") (class "Default")
      (node (ref "U1") (pin "63") (pinfunction "V8_63") (pintype "passive"))
    )
    (net (code "70") (name "/OUT2") (class "Default")
      (node (ref "U1") (pin "61") (pinfunction "V7_61") (pintype "passive"))
    )
    (net (code "71") (name "/OUT3") (class "Default")
      (node (ref "U1") (pin "59") (pinfunction "V6_59") (pintype "passive"))
    )
    (net (code "72") (name "/OUT4") (class "Default")
      (node (ref "U1") (pin "57") (pinfunction "V5_57") (pintype "passive"))
    )
    (net (code "73") (name "/OUT5") (class "Default")
      (node (ref "U1") (pin "55") (pinfunction "V4_55") (pintype "passive"))
    )
    (net (code "74") (name "/OUT6") (class "Default")
      (node (ref "U1") (pin "53") (pinfunction "V3_53") (pintype "passive"))
    )
    (net (code "75") (name "/OUT7") (class "Default")
      (node (ref "U1") (pin "51") (pinfunction "V2_51") (pintype "passive"))
    )
    (net (code "76") (name "/OUT8") (class "Default")
      (node (ref "U1") (pin "49") (pinfunction "V1_49") (pintype "passive"))
    )
    (net (code "78") (name "/PART1_BUSY") (class "Default")
      (node (ref "R128") (pin "2") (pinfunction "2_2") (pintype "passive"))
    )
    (net (code "79") (name "/PART1_CLK") (class "Default")
      (node (ref "R126") (pin "2") (pinfunction "2_2") (pintype "passive"))
    )
    (net (code "80") (name "/PART1_CS") (class "Default")
      (node (ref "R127") (pin "2") (pinfunction "2_2") (pintype "passive"))
    )
    (net (code "81") (name "/PART1_DO") (class "Default")
      (node (ref "R129") (pin "2") (pinfunction "2_2") (pintype "passive"))
    )
    (net (code "82") (name "/PART1_REST") (class "Default")
      (node (ref "R125") (pin "2") (pinfunction "2_2") (pintype "passive"))
    )
    (net (code "83") (name "/REFIN") (class "Default")
      (node (ref "C15") (pin "1") (pinfunction "1_1") (pintype "passive"))
      (node (ref "C31") (pin "1") (pinfunction "1_1") (pintype "passive"))
      (node (ref "C32") (pin "2") (pinfunction "2_2") (pintype "passive"))
      (node (ref "U1") (pin "42") (pinfunction "REFIN/REFOUT_42") (pintype "passive"))
      (node (ref "U11") (pin "6") (pinfunction "Vout_6") (pintype "passive"))
    )
    (net (code "84") (name "/REFSEL") (class "Default")
      (node (ref "R12") (pin "2") (pinfunction "2_2") (pintype "passive"))
      (node (ref "R13") (pin "2") (pinfunction "2_2") (pintype "passive"))
      (node (ref "U1") (pin "34") (pinfunction "REF_SELECT_34") (pintype "passive"))
    )
    (net (code "85") (name "/REST") (class "Default")
      (node (ref "R9") (pin "1") (pinfunction "1_1") (pintype "passive"))
      (node (ref "U1") (pin "11") (pinfunction "RESET_11") (pintype "passive"))
    )
    (net (code "86") (name "5V_0") (class "Default")
      (node (ref "C175") (pin "2") (pinfunction "2_2") (pintype "passive"))
      (node (ref "U10") (pin "1") (pinfunction "VDD1_1") (pintype "passive"))
    )
    (net (code "87") (name "40V") (class "Default")
      (node (ref "C157") (pin "1") (pinfunction "1_1") (pintype "passive"))
      (node (ref "C158") (pin "1") (pinfunction "1_1") (pintype "passive"))
      (node (ref "C159") (pin "2") (pinfunction "2_2") (pintype "passive"))
      (node (ref "C160") (pin "1") (pinfunction "1_1") (pintype "passive"))
      (node (ref "C162") (pin "1") (pinfunction "1_1") (pintype "passive"))
      (node (ref "C164") (pin "1") (pinfunction "1_1") (pintype "passive"))
      (node (ref "C166") (pin "1") (pinfunction "1_1") (pintype "passive"))
      (node (ref "C168") (pin "1") (pinfunction "1_1") (pintype "passive"))
      (node (ref "C170") (pin "1") (pinfunction "1_1") (pintype "passive"))
      (node (ref "C172") (pin "1") (pinfunction "1_1") (pintype "passive"))
      (node (ref "R119") (pin "2") (pinfunction "2_2") (pintype "passive"))
      (node (ref "U2") (pin "14") (pinfunction "VDD_14") (pintype "passive"))
      (node (ref "U3") (pin "14") (pinfunction "VDD_14") (pintype "passive"))
      (node (ref "U4") (pin "14") (pinfunction "VDD_14") (pintype "passive"))
      (node (ref "U5") (pin "14") (pinfunction "VDD_14") (pintype "passive"))
      (node (ref "U6") (pin "14") (pinfunction "VDD_14") (pintype "passive"))
      (node (ref "U7") (pin "14") (pinfunction "VDD_14") (pintype "passive"))
      (node (ref "U8") (pin "14") (pinfunction "VDD_14") (pintype "passive"))
      (node (ref "U9") (pin "14") (pinfunction "VDD_14") (pintype "passive"))
    )
    (net (code "88") (name "AGND_1") (class "Default")
      (node (ref "C146") (pin "2") (pinfunction "2_2") (pintype "passive"))
      (node (ref "C15") (pin "2") (pinfunction "2_2") (pintype "passive"))
      (node (ref "C16") (pin "2") (pinfunction "2_2") (pintype "passive"))
      (node (ref "C17") (pin "2") (pinfunction "2_2") (pintype "passive"))
      (node (ref "C18") (pin "2") (pinfunction "2_2") (pintype "passive"))
      (node (ref "C194") (pin "2") (pinfunction "2_2") (pintype "passive"))
      (node (ref "C195") (pin "2") (pinfunction "2_2") (pintype "passive"))
      (node (ref "C196") (pin "2") (pinfunction "2_2") (pintype "passive"))
      (node (ref "C199") (pin "2") (pinfunction "2_2") (pintype "passive"))
      (node (ref "C200") (pin "2") (pinfunction "2_2") (pintype "passive"))
      (node (ref "C29") (pin "2") (pinfunction "2_2") (pintype "passive"))
      (node (ref "C31") (pin "2") (pinfunction "2_2") (pintype "passive"))
      (node (ref "C32") (pin "1") (pinfunction "1_1") (pintype "passive"))
      (node (ref "C7") (pin "1") (pinfunction "1_1") (pintype "passive"))
      (node (ref "C8") (pin "1") (pinfunction "1_1") (pintype "passive"))
      (node (ref "C9") (pin "2") (pinfunction "2_2") (pintype "passive"))
      (node (ref "R12") (pin "1") (pinfunction "1_1") (pintype "passive"))
      (node (ref "R172") (pin "2") (pinfunction "2_2") (pintype "passive"))
      (node (ref "SW1") (pin "1") (pinfunction "1_1") (pintype "passive"))
      (node (ref "SW1") (pin "3") (pinfunction "3_3") (pintype "passive"))
      (node (ref "SW1") (pin "5") (pinfunction "5_5") (pintype "passive"))
      (node (ref "U1") (pin "16") (pinfunction "DB0_16") (pintype "passive"))
      (node (ref "U1") (pin "17") (pinfunction "DB1_17") (pintype "passive"))
      (node (ref "U1") (pin "18") (pinfunction "DB2_18") (pintype "passive"))
      (node (ref "U1") (pin "19") (pinfunction "DB3_19") (pintype "passive"))
      (node (ref "U1") (pin "2") (pinfunction "AGND_2") (pintype "passive"))
      (node (ref "U1") (pin "20") (pinfunction "DB4_20") (pintype "passive"))
      (node (ref "U1") (pin "21") (pinfunction "DB5_21") (pintype "passive"))
      (node (ref "U1") (pin "22") (pinfunction "DB6_22") (pintype "passive"))
      (node (ref "U1") (pin "26") (pinfunction "AGND_26") (pintype "passive"))
      (node (ref "U1") (pin "27") (pinfunction "DB9_27") (pintype "passive"))
      (node (ref "U1") (pin "28") (pinfunction "DB10_28") (pintype "passive"))
      (node (ref "U1") (pin "29") (pinfunction "DB11_29") (pintype "passive"))
      (node (ref "U1") (pin "30") (pinfunction "DB12_30") (pintype "passive"))
      (node (ref "U1") (pin "31") (pinfunction "DB13_31") (pintype "passive"))
      (node (ref "U1") (pin "32") (pinfunction "DB14/HBEN_32") (pintype "passive"))
      (node (ref "U1") (pin "33") (pinfunction "DB15/BYTE_SEL_33") (pintype "passive"))
      (node (ref "U1") (pin "35") (pinfunction "AGND_35") (pintype "passive"))
      (node (ref "U1") (pin "40") (pinfunction "AGND_40") (pintype "passive"))
      (node (ref "U1") (pin "41") (pinfunction "AGND_41") (pintype "passive"))
      (node (ref "U1") (pin "43") (pinfunction "REFGND_43") (pintype "passive"))
      (node (ref "U1") (pin "46") (pinfunction "REFGND_46") (pintype "passive"))
      (node (ref "U1") (pin "47") (pinfunction "AGND_47") (pintype "passive"))
      (node (ref "U1") (pin "50") (pinfunction "V1GND_50") (pintype "passive"))
      (node (ref "U1") (pin "52") (pinfunction "V2GND_52") (pintype "passive"))
      (node (ref "U1") (pin "54") (pinfunction "V3GND_54") (pintype "passive"))
      (node (ref "U1") (pin "56") (pinfunction "V4GND_56") (pintype "passive"))
      (node (ref "U1") (pin "58") (pinfunction "V5GND_58") (pintype "passive"))
      (node (ref "U1") (pin "60") (pinfunction "V6GND_60") (pintype "passive"))
      (node (ref "U1") (pin "62") (pinfunction "V7GND_62") (pintype "passive"))
      (node (ref "U1") (pin "64") (pinfunction "V8GND_64") (pintype "passive"))
      (node (ref "U1") (pin "8") (pinfunction "RANGE_8") (pintype "passive"))
      (node (ref "U11") (pin "4") (pinfunction "GND_4") (pintype "passive"))
    )
    (net (code "89") (name "DGND_1") (class "Default")
      (node (ref "C141") (pin "1") (pinfunction "1_1") (pintype "passive"))
      (node (ref "C198") (pin "1") (pinfunction "1_1") (pintype "passive"))
      (node (ref "C199") (pin "1") (pinfunction "1_1") (pintype "passive"))
      (node (ref "C2") (pin "2") (pinfunction "2_2") (pintype "passive"))
      (node (ref "C200") (pin "1") (pinfunction "1_1") (pintype "passive"))
      (node (ref "R172") (pin "1") (pinfunction "1_1") (pintype "passive"))
      (node (ref "R173") (pin "1") (pinfunction "1_1") (pintype "passive"))
      (node (ref "U10") (pin "9") (pinfunction "GND2_9") (pintype "passive"))
    )
    (net (code "90") (name "DVCC_1") (class "Default")
      (node (ref "C8") (pin "2") (pinfunction "2_2") (pintype "passive"))
      (node (ref "R1") (pin "1") (pinfunction "1_1") (pintype "passive"))
      (node (ref "R13") (pin "1") (pinfunction "1_1") (pintype "passive"))
      (node (ref "R179") (pin "1") (pinfunction "1_1") (pintype "passive"))
      (node (ref "R2") (pin "1") (pinfunction "1_1") (pintype "passive"))
      (node (ref "R3") (pin "1") (pinfunction "1_1") (pintype "passive"))
      (node (ref "R4") (pin "2") (pinfunction "2_2") (pintype "passive"))
      (node (ref "R5") (pin "2") (pinfunction "2_2") (pintype "passive"))
      (node (ref "U1") (pin "23") (pinfunction "VDRIVE_23") (pintype "passive"))
    )
    (net (code "91") (name "GND") (class "Default")
      (node (ref "C175") (pin "1") (pinfunction "1_1") (pintype "passive"))
      (node (ref "U10") (pin "8") (pinfunction "GND1_8") (pintype "passive"))
    )
    (net (code "92") (name "GND_FC") (class "Default")
      (node (ref "C13") (pin "2") (pinfunction "2_2") (pintype "passive"))
      (node (ref "C14") (pin "2") (pinfunction "2_2") (pintype "passive"))
      (node (ref "DB1") (pin "2") (pinfunction "2_2") (pintype "passive"))
      (node (ref "DB1") (pin "21") (pinfunction "21_21") (pintype "passive"))
      (node (ref "R120") (pin "1") (pinfunction "1_1") (pintype "passive"))
    )
    (net (code "93") (name "GND_FC1") (class "Default")
      (node (ref "C141") (pin "2") (pinfunction "2_2") (pintype "passive"))
      (node (ref "C157") (pin "2") (pinfunction "2_2") (pintype "passive"))
      (node (ref "C158") (pin "2") (pinfunction "2_2") (pintype "passive"))
      (node (ref "C159") (pin "1") (pinfunction "1_1") (pintype "passive"))
      (node (ref "C160") (pin "2") (pinfunction "2_2") (pintype "passive"))
      (node (ref "C162") (pin "2") (pinfunction "2_2") (pintype "passive"))
      (node (ref "C164") (pin "2") (pinfunction "2_2") (pintype "passive"))
      (node (ref "C166") (pin "2") (pinfunction "2_2") (pintype "passive"))
      (node (ref "C168") (pin "2") (pinfunction "2_2") (pintype "passive"))
      (node (ref "C170") (pin "2") (pinfunction "2_2") (pintype "passive"))
      (node (ref "C172") (pin "2") (pinfunction "2_2") (pintype "passive"))
      (node (ref "C198") (pin "2") (pinfunction "2_2") (pintype "passive"))
      (node (ref "DB1") (pin "38") (pinfunction "38_38") (pintype "passive"))
      (node (ref "DB1") (pin "39") (pinfunction "39_39") (pintype "passive"))
      (node (ref "R120") (pin "2") (pinfunction "2_2") (pintype "passive"))
      (node (ref "R173") (pin "2") (pinfunction "2_2") (pintype "passive"))
      (node (ref "U2") (pin "15") (pinfunction "GND_15") (pintype "passive"))
      (node (ref "U2") (pin "3") (pinfunction "VSS_3") (pintype "passive"))
      (node (ref "U3") (pin "15") (pinfunction "GND_15") (pintype "passive"))
      (node (ref "U3") (pin "3") (pinfunction "VSS_3") (pintype "passive"))
      (node (ref "U4") (pin "15") (pinfunction "GND_15") (pintype "passive"))
      (node (ref "U4") (pin "3") (pinfunction "VSS_3") (pintype "passive"))
      (node (ref "U5") (pin "15") (pinfunction "GND_15") (pintype "passive"))
      (node (ref "U5") (pin "3") (pinfunction "VSS_3") (pintype "passive"))
      (node (ref "U6") (pin "15") (pinfunction "GND_15") (pintype "passive"))
      (node (ref "U6") (pin "3") (pinfunction "VSS_3") (pintype "passive"))
      (node (ref "U7") (pin "15") (pinfunction "GND_15") (pintype "passive"))
      (node (ref "U7") (pin "3") (pinfunction "VSS_3") (pintype "passive"))
      (node (ref "U8") (pin "15") (pinfunction "GND_15") (pintype "passive"))
      (node (ref "U8") (pin "3") (pinfunction "VSS_3") (pintype "passive"))
      (node (ref "U9") (pin "15") (pinfunction "GND_15") (pintype "passive"))
      (node (ref "U9") (pin "3") (pinfunction "VSS_3") (pintype "passive"))
    )
    (net (code "94") (name "Net-(A9-Pad1)") (class "Default")
      (node (ref "A9") (pin "1") (pinfunction "1_1") (pintype "passive"))
      (node (ref "DB1") (pin "22") (pinfunction "22_22") (pintype "passive"))
    )
    (net (code "95") (name "Net-(A9-Pad3)") (class "Default")
      (node (ref "A9") (pin "3") (pinfunction "3_3") (pintype "passive"))
      (node (ref "DB1") (pin "4") (pinfunction "4_4") (pintype "passive"))
    )
    (net (code "96") (name "Net-(A9-Pad5)") (class "Default")
      (node (ref "A9") (pin "5") (pinfunction "5_5") (pintype "passive"))
      (node (ref "DB1") (pin "23") (pinfunction "23_23") (pintype "passive"))
    )
    (net (code "97") (name "Net-(A9-Pad7)") (class "Default")
      (node (ref "A9") (pin "7") (pinfunction "7_7") (pintype "passive"))
      (node (ref "DB1") (pin "5") (pinfunction "5_5") (pintype "passive"))
    )
    (net (code "98") (name "Net-(A10-Pad1)") (class "Default")
      (node (ref "A10") (pin "1") (pinfunction "1_1") (pintype "passive"))
      (node (ref "DB1") (pin "24") (pinfunction "24_24") (pintype "passive"))
    )
    (net (code "99") (name "Net-(A10-Pad3)") (class "Default")
      (node (ref "A10") (pin "3") (pinfunction "3_3") (pintype "passive"))
      (node (ref "DB1") (pin "6") (pinfunction "6_6") (pintype "passive"))
    )
    (net (code "100") (name "Net-(A10-Pad5)") (class "Default")
      (node (ref "A10") (pin "5") (pinfunction "5_5") (pintype "passive"))
      (node (ref "DB1") (pin "25") (pinfunction "25_25") (pintype "passive"))
    )
    (net (code "101") (name "Net-(A10-Pad7)") (class "Default")
      (node (ref "A10") (pin "7") (pinfunction "7_7") (pintype "passive"))
      (node (ref "DB1") (pin "7") (pinfunction "7_7") (pintype "passive"))
    )
    (net (code "102") (name "Net-(A11-Pad1)") (class "Default")
      (node (ref "A11") (pin "1") (pinfunction "1_1") (pintype "passive"))
      (node (ref "DB1") (pin "26") (pinfunction "26_26") (pintype "passive"))
    )
    (net (code "103") (name "Net-(A11-Pad3)") (class "Default")
      (node (ref "A11") (pin "3") (pinfunction "3_3") (pintype "passive"))
      (node (ref "DB1") (pin "8") (pinfunction "8_8") (pintype "passive"))
    )
    (net (code "104") (name "Net-(A11-Pad5)") (class "Default")
      (node (ref "A11") (pin "5") (pinfunction "5_5") (pintype "passive"))
      (node (ref "DB1") (pin "27") (pinfunction "27_27") (pintype "passive"))
    )
    (net (code "105") (name "Net-(A11-Pad7)") (class "Default")
      (node (ref "A11") (pin "7") (pinfunction "7_7") (pintype "passive"))
      (node (ref "DB1") (pin "9") (pinfunction "9_9") (pintype "passive"))
    )
    (net (code "106") (name "Net-(A12-Pad1)") (class "Default")
      (node (ref "A12") (pin "1") (pinfunction "1_1") (pintype "passive"))
      (node (ref "DB1") (pin "28") (pinfunction "28_28") (pintype "passive"))
    )
    (net (code "107") (name "Net-(A12-Pad3)") (class "Default")
      (node (ref "A12") (pin "3") (pinfunction "3_3") (pintype "passive"))
      (node (ref "DB1") (pin "10") (pinfunction "10_10") (pintype "passive"))
    )
    (net (code "108") (name "Net-(A12-Pad5)") (class "Default")
      (node (ref "A12") (pin "5") (pinfunction "5_5") (pintype "passive"))
      (node (ref "DB1") (pin "29") (pinfunction "29_29") (pintype "passive"))
    )
    (net (code "109") (name "Net-(A12-Pad7)") (class "Default")
      (node (ref "A12") (pin "7") (pinfunction "7_7") (pintype "passive"))
      (node (ref "DB1") (pin "11") (pinfunction "11_11") (pintype "passive"))
    )
    (net (code "110") (name "Net-(A13-Pad1)") (class "Default")
      (node (ref "A13") (pin "1") (pinfunction "1_1") (pintype "passive"))
      (node (ref "DB1") (pin "30") (pinfunction "30_30") (pintype "passive"))
    )
    (net (code "111") (name "Net-(A13-Pad3)") (class "Default")
      (node (ref "A13") (pin "3") (pinfunction "3_3") (pintype "passive"))
      (node (ref "DB1") (pin "12") (pinfunction "12_12") (pintype "passive"))
    )
    (net (code "112") (name "Net-(A13-Pad5)") (class "Default")
      (node (ref "A13") (pin "5") (pinfunction "5_5") (pintype "passive"))
      (node (ref "DB1") (pin "31") (pinfunction "31_31") (pintype "passive"))
    )
    (net (code "113") (name "Net-(A13-Pad7)") (class "Default")
      (node (ref "A13") (pin "7") (pinfunction "7_7") (pintype "passive"))
      (node (ref "DB1") (pin "13") (pinfunction "13_13") (pintype "passive"))
    )
    (net (code "114") (name "Net-(A14-Pad1)") (class "Default")
      (node (ref "A14") (pin "1") (pinfunction "1_1") (pintype "passive"))
      (node (ref "DB1") (pin "32") (pinfunction "32_32") (pintype "passive"))
    )
    (net (code "115") (name "Net-(A14-Pad3)") (class "Default")
      (node (ref "A14") (pin "3") (pinfunction "3_3") (pintype "passive"))
      (node (ref "DB1") (pin "14") (pinfunction "14_14") (pintype "passive"))
    )
    (net (code "116") (name "Net-(A14-Pad5)") (class "Default")
      (node (ref "A14") (pin "5") (pinfunction "5_5") (pintype "passive"))
      (node (ref "DB1") (pin "33") (pinfunction "33_33") (pintype "passive"))
    )
    (net (code "117") (name "Net-(A14-Pad7)") (class "Default")
      (node (ref "A14") (pin "7") (pinfunction "7_7") (pintype "passive"))
      (node (ref "DB1") (pin "15") (pinfunction "15_15") (pintype "passive"))
    )
    (net (code "118") (name "Net-(A15-Pad1)") (class "Default")
      (node (ref "A15") (pin "1") (pinfunction "1_1") (pintype "passive"))
      (node (ref "DB1") (pin "34") (pinfunction "34_34") (pintype "passive"))
    )
    (net (code "119") (name "Net-(A15-Pad3)") (class "Default")
      (node (ref "A15") (pin "3") (pinfunction "3_3") (pintype "passive"))
      (node (ref "DB1") (pin "16") (pinfunction "16_16") (pintype "passive"))
    )
    (net (code "120") (name "Net-(A15-Pad5)") (class "Default")
      (node (ref "A15") (pin "5") (pinfunction "5_5") (pintype "passive"))
      (node (ref "DB1") (pin "35") (pinfunction "35_35") (pintype "passive"))
    )
    (net (code "121") (name "Net-(A15-Pad7)") (class "Default")
      (node (ref "A15") (pin "7") (pinfunction "7_7") (pintype "passive"))
      (node (ref "DB1") (pin "17") (pinfunction "17_17") (pintype "passive"))
    )
    (net (code "122") (name "Net-(A16-Pad1)") (class "Default")
      (node (ref "A16") (pin "1") (pinfunction "1_1") (pintype "passive"))
      (node (ref "DB1") (pin "36") (pinfunction "36_36") (pintype "passive"))
    )
    (net (code "123") (name "Net-(A16-Pad3)") (class "Default")
      (node (ref "A16") (pin "3") (pinfunction "3_3") (pintype "passive"))
      (node (ref "DB1") (pin "18") (pinfunction "18_18") (pintype "passive"))
    )
    (net (code "124") (name "Net-(A16-Pad5)") (class "Default")
      (node (ref "A16") (pin "5") (pinfunction "5_5") (pintype "passive"))
      (node (ref "DB1") (pin "37") (pinfunction "37_37") (pintype "passive"))
    )
    (net (code "125") (name "Net-(A16-Pad7)") (class "Default")
      (node (ref "A16") (pin "7") (pinfunction "7_7") (pintype "passive"))
      (node (ref "DB1") (pin "19") (pinfunction "19_19") (pintype "passive"))
    )
    (net (code "126") (name "Net-(C17-Pad1)") (class "Default")
      (node (ref "C17") (pin "1") (pinfunction "1_1") (pintype "passive"))
      (node (ref "U1") (pin "39") (pinfunction "REGCAP_39") (pintype "passive"))
    )
    (net (code "127") (name "Net-(C18-Pad1)") (class "Default")
      (node (ref "C18") (pin "1") (pinfunction "1_1") (pintype "passive"))
      (node (ref "U1") (pin "36") (pinfunction "REGCAP_36") (pintype "passive"))
    )
    (net (code "128") (name "Net-(DB1-Pad3)") (class "Default")
      (node (ref "DB1") (pin "3") (pinfunction "3_3") (pintype "passive"))
      (node (ref "R118") (pin "2") (pinfunction "2_2") (pintype "passive"))
    )
    (net (code "129") (name "Net-(U1-REFCAPA)") (class "Default")
      (node (ref "C16") (pin "1") (pinfunction "1_1") (pintype "passive"))
      (node (ref "U1") (pin "44") (pinfunction "REFCAPA_44") (pintype "passive"))
      (node (ref "U1") (pin "45") (pinfunction "REFCAPB_45") (pintype "passive"))
    )
    (net (code "130") (name "Net-(U1-~{PAR}{slash}SER{slash}BYTE_SEL)") (class "Default")
      (node (ref "R5") (pin "1") (pinfunction "1_1") (pintype "passive"))
      (node (ref "U1") (pin "6") (pinfunction "~{PAR}/SER/BYTE_SEL_6") (pintype "passive"))
    )
    (net (code "131") (name "Net-(U1-~{STBY})") (class "Default")
      (node (ref "R4") (pin "1") (pinfunction "1_1") (pintype "passive"))
      (node (ref "U1") (pin "7") (pinfunction "~{STBY}_7") (pintype "passive"))
    )
    (net (code "132") (name "Net-(U10-INA)") (class "Default")
      (node (ref "R125") (pin "1") (pinfunction "1_1") (pintype "passive"))
      (node (ref "U10") (pin "2") (pinfunction "INA_2") (pintype "passive"))
    )
    (net (code "133") (name "Net-(U10-INB)") (class "Default")
      (node (ref "R126") (pin "1") (pinfunction "1_1") (pintype "passive"))
      (node (ref "U10") (pin "3") (pinfunction "INB_3") (pintype "passive"))
    )
    (net (code "134") (name "Net-(U10-INC)") (class "Default")
      (node (ref "R127") (pin "1") (pinfunction "1_1") (pintype "passive"))
      (node (ref "U10") (pin "4") (pinfunction "INC_4") (pintype "passive"))
    )
    (net (code "135") (name "Net-(U10-IND)") (class "Default")
      (node (ref "R123") (pin "2") (pinfunction "2_2") (pintype "passive"))
      (node (ref "U10") (pin "12") (pinfunction "IND_12") (pintype "passive"))
    )
    (net (code "136") (name "Net-(U10-INE)") (class "Default")
      (node (ref "R124") (pin "2") (pinfunction "2_2") (pintype "passive"))
      (node (ref "U10") (pin "11") (pinfunction "INE_11") (pintype "passive"))
    )
    (net (code "137") (name "Net-(U10-OUTA)") (class "Default")
      (node (ref "R9") (pin "2") (pinfunction "2_2") (pintype "passive"))
      (node (ref "U10") (pin "15") (pinfunction "OUTA_15") (pintype "passive"))
    )
    (net (code "138") (name "Net-(U10-OUTB)") (class "Default")
      (node (ref "R121") (pin "2") (pinfunction "2_2") (pintype "passive"))
      (node (ref "U10") (pin "14") (pinfunction "OUTB_14") (pintype "passive"))
    )
    (net (code "139") (name "Net-(U10-OUTC)") (class "Default")
      (node (ref "R122") (pin "2") (pinfunction "2_2") (pintype "passive"))
      (node (ref "U10") (pin "13") (pinfunction "OUTC_13") (pintype "passive"))
    )
    (net (code "140") (name "Net-(U10-OUTD)") (class "Default")
      (node (ref "R128") (pin "1") (pinfunction "1_1") (pintype "passive"))
      (node (ref "U10") (pin "5") (pinfunction "OUTD_5") (pintype "passive"))
    )
    (net (code "141") (name "Net-(U10-OUTE)") (class "Default")
      (node (ref "R129") (pin "1") (pinfunction "1_1") (pintype "passive"))
      (node (ref "U10") (pin "6") (pinfunction "OUTE_6") (pintype "passive"))
    )
    (net (code "142") (name "VCC_1") (class "Default")
      (node (ref "C2") (pin "1") (pinfunction "1_1") (pintype "passive"))
      (node (ref "U10") (pin "16") (pinfunction "VDD2_16") (pintype "passive"))
    )
    (net (code "143") (name "V_FC") (class "Default")
      (node (ref "C13") (pin "1") (pinfunction "1_1") (pintype "passive"))
      (node (ref "C14") (pin "1") (pinfunction "1_1") (pintype "passive"))
      (node (ref "DB1") (pin "1") (pinfunction "1_1") (pintype "passive"))
      (node (ref "DB1") (pin "20") (pinfunction "20_20") (pintype "passive"))
      (node (ref "R119") (pin "1") (pinfunction "1_1") (pintype "passive"))
    )
    (net (code "144") (name "unconnected-(U1-FRSTDATA-Pad15)") (class "Default")
      (node (ref "U1") (pin "15") (pinfunction "FRSTDATA_15") (pintype "passive"))
    )
    (net (code "145") (name "unconnected-(U10-NC-Pad7)") (class "Default")
      (node (ref "U10") (pin "7") (pinfunction "NC_7") (pintype "passive"))
    )
    (net (code "146") (name "unconnected-(U10-NC-Pad10)") (class "Default")
      (node (ref "U10") (pin "10") (pinfunction "NC_10") (pintype "passive"))
    )
    (net (code "147") (name "unconnected-(U11-DNC-Pad1)") (class "Default")
      (node (ref "U11") (pin "1") (pinfunction "DNC_1") (pintype "passive"))
    )
    (net (code "148") (name "unconnected-(U11-DNC-Pad8)") (class "Default")
      (node (ref "U11") (pin "8") (pinfunction "DNC_8") (pintype "passive"))
    )
    (net (code "149") (name "unconnected-(U11-NC-Pad7)") (class "Default")
      (node (ref "U11") (pin "7") (pinfunction "NC_7") (pintype "passive"))
    )
    (net (code "150") (name "unconnected-(U11-TEMP-Pad3)") (class "Default")
      (node (ref "U11") (pin "3") (pinfunction "TEMP_3") (pintype "passive"))
    )
    (net (code "151") (name "unconnected-(U11-TRIM{slash}NR-Pad5)") (class "Default")
      (node (ref "U11") (pin "5") (pinfunction "TRIM/NR_5") (pintype "passive"))
    )
  )
)
